# motoko_ice_dragon_v1.net
KiCad netlist of a schematic drawn in EAGLE
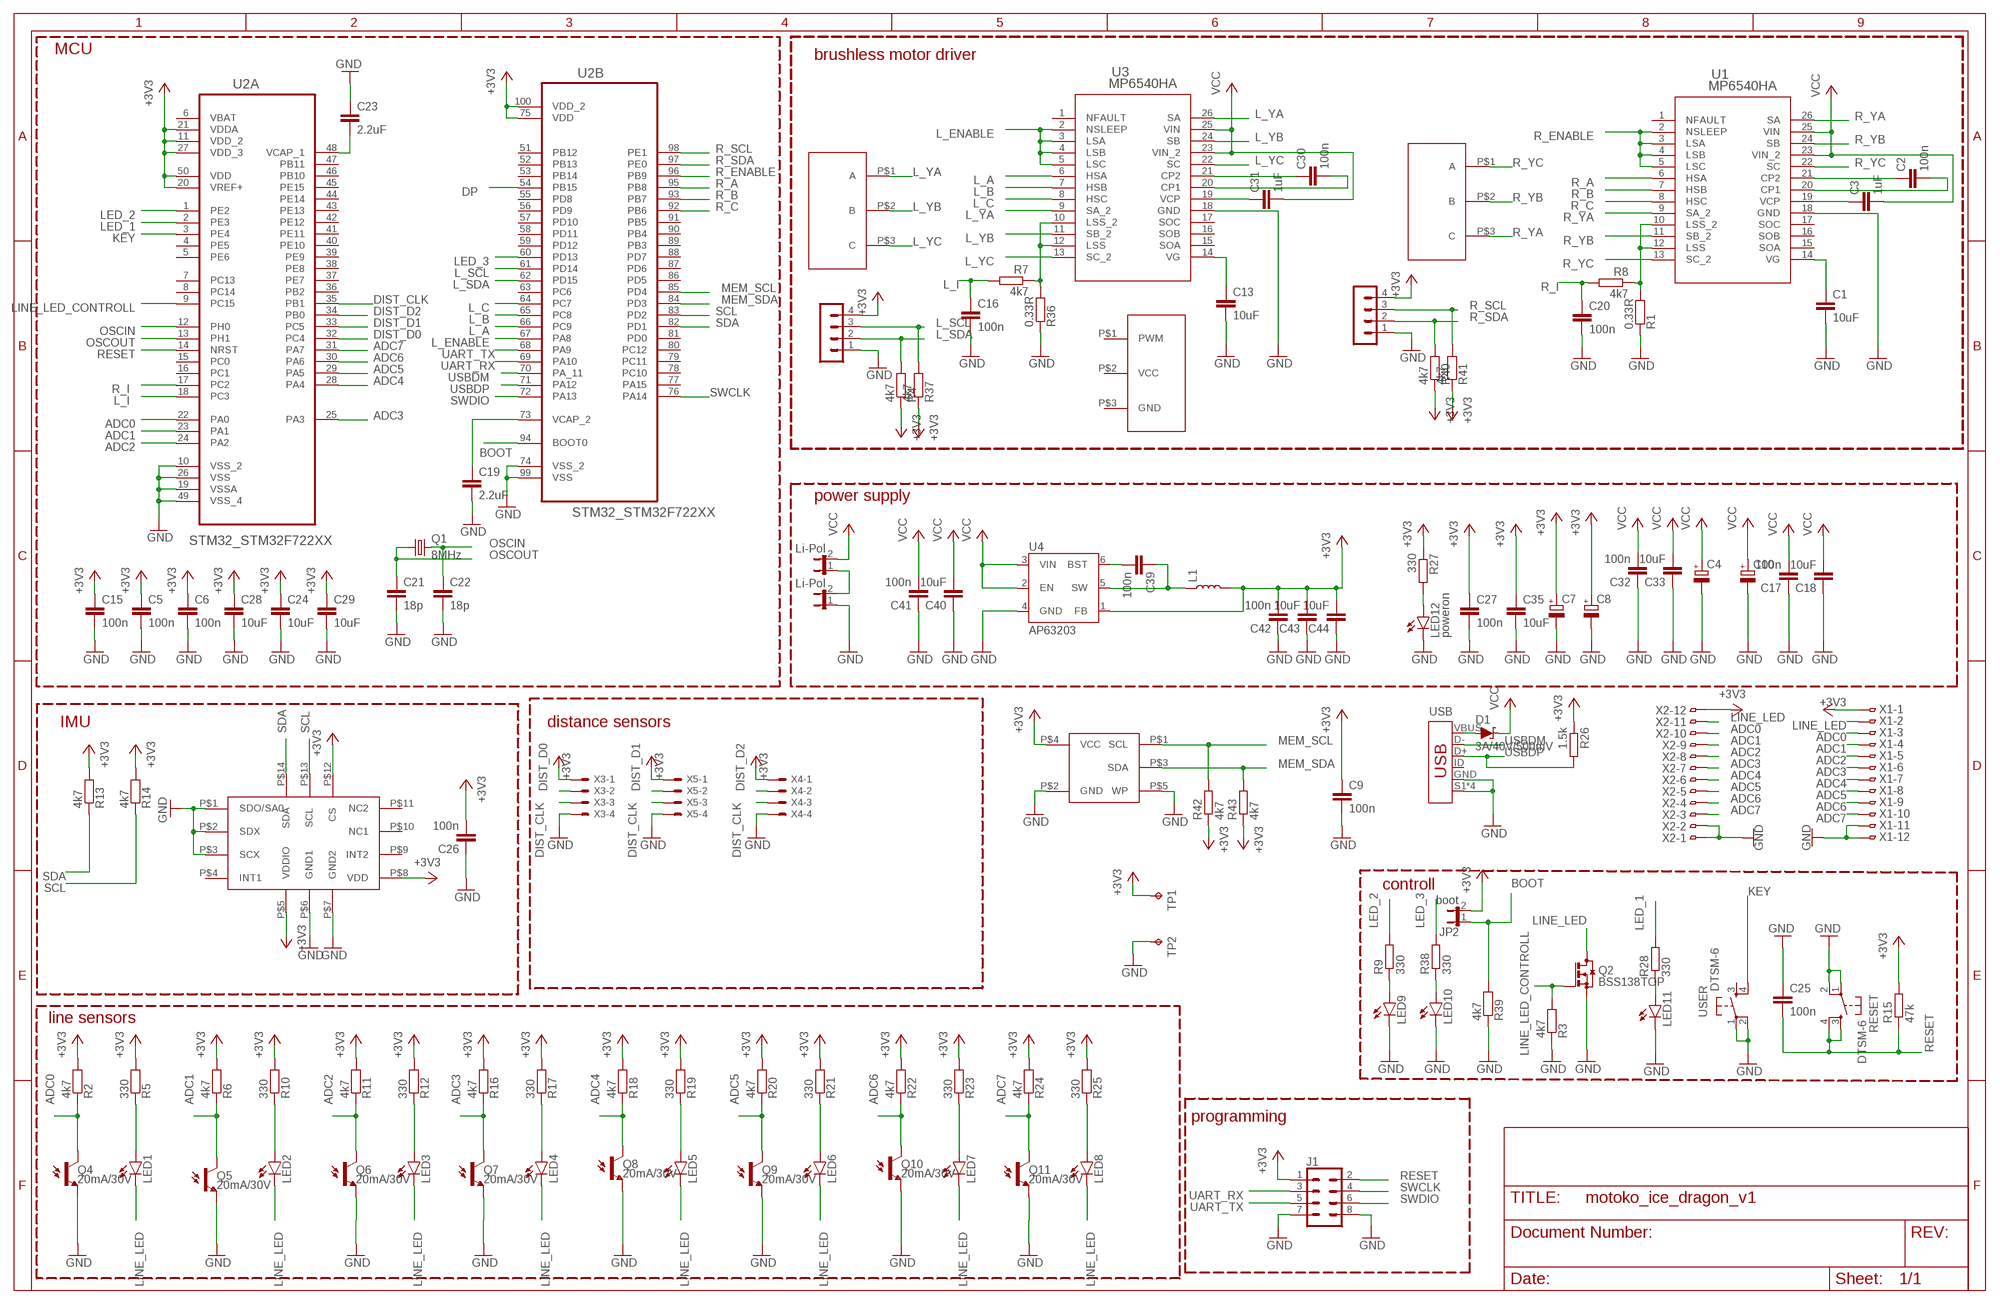
[diagram p0: schematic, sheet 1]

(export (version "E")
  (design (tool "Eeschema 10.0.6"))
  (components
    (comp (ref "C1")
      (value "10uF")
      (footprint "eagle-import:C0805")
      (libsource (lib "eagle-import") (part "C-EUC0805"))
    )
    (comp (ref "C2")
      (value "100n")
      (footprint "eagle-import:C0805")
      (libsource (lib "eagle-import") (part "C-EUC0805"))
    )
    (comp (ref "C3")
      (value "1uF")
      (footprint "eagle-import:C0805")
      (libsource (lib "eagle-import") (part "C-EUC0805"))
    )
    (comp (ref "C4")
      (value "CPOL-EU085CS-1AR")
      (footprint "eagle-import:085CS_1AR")
      (libsource (lib "eagle-import") (part "CPOL-EU085CS-1AR"))
    )
    (comp (ref "C5")
      (value "100n")
      (footprint "eagle-import:C0805")
      (libsource (lib "eagle-import") (part "C-EUC0805"))
    )
    (comp (ref "C6")
      (value "100n")
      (footprint "eagle-import:C0805")
      (libsource (lib "eagle-import") (part "C-EUC0805"))
    )
    (comp (ref "C7")
      (value "CPOL-EU085CS-1AR")
      (footprint "eagle-import:085CS_1AR")
      (libsource (lib "eagle-import") (part "CPOL-EU085CS-1AR"))
    )
    (comp (ref "C8")
      (value "CPOL-EU085CS-1AR")
      (footprint "eagle-import:085CS_1AR")
      (libsource (lib "eagle-import") (part "CPOL-EU085CS-1AR"))
    )
    (comp (ref "C9")
      (value "100n")
      (footprint "eagle-import:C0805")
      (libsource (lib "eagle-import") (part "C-EUC0805"))
    )
    (comp (ref "C10")
      (value "CPOL-EU085CS-1AR")
      (footprint "eagle-import:085CS_1AR")
      (libsource (lib "eagle-import") (part "CPOL-EU085CS-1AR"))
    )
    (comp (ref "C13")
      (value "10uF")
      (footprint "eagle-import:C0805")
      (libsource (lib "eagle-import") (part "C-EUC0805"))
    )
    (comp (ref "C15")
      (value "100n")
      (footprint "eagle-import:C0805")
      (libsource (lib "eagle-import") (part "C-EUC0805"))
    )
    (comp (ref "C16")
      (value "100n")
      (footprint "eagle-import:C0805")
      (libsource (lib "eagle-import") (part "C-EUC0805"))
    )
    (comp (ref "C17")
      (value "100n")
      (footprint "eagle-import:C0805")
      (libsource (lib "eagle-import") (part "C-EUC0805"))
    )
    (comp (ref "C18")
      (value "10uF")
      (footprint "eagle-import:C0805")
      (libsource (lib "eagle-import") (part "C-EUC0805"))
    )
    (comp (ref "C19")
      (value "2.2uF")
      (footprint "eagle-import:C0805")
      (libsource (lib "eagle-import") (part "C-EUC0805"))
    )
    (comp (ref "C20")
      (value "100n")
      (footprint "eagle-import:C0805")
      (libsource (lib "eagle-import") (part "C-EUC0805"))
    )
    (comp (ref "C21")
      (value "18p")
      (footprint "eagle-import:C0805")
      (libsource (lib "eagle-import") (part "C-EUC0805"))
    )
    (comp (ref "C22")
      (value "18p")
      (footprint "eagle-import:C0805")
      (libsource (lib "eagle-import") (part "C-EUC0805"))
    )
    (comp (ref "C23")
      (value "2.2uF")
      (footprint "eagle-import:C0805")
      (libsource (lib "eagle-import") (part "C-EUC0805"))
    )
    (comp (ref "C24")
      (value "10uF")
      (footprint "eagle-import:C0805")
      (libsource (lib "eagle-import") (part "C-EUC0805"))
    )
    (comp (ref "C25")
      (value "100n")
      (footprint "eagle-import:C0805")
      (libsource (lib "eagle-import") (part "C-EUC0805"))
    )
    (comp (ref "C26")
      (value "100n")
      (footprint "eagle-import:C0805")
      (libsource (lib "eagle-import") (part "C-EUC0805"))
    )
    (comp (ref "C27")
      (value "100n")
      (footprint "eagle-import:C0805")
      (libsource (lib "eagle-import") (part "C-EUC0805"))
    )
    (comp (ref "C28")
      (value "10uF")
      (footprint "eagle-import:C0805")
      (libsource (lib "eagle-import") (part "C-EUC0805"))
    )
    (comp (ref "C29")
      (value "10uF")
      (footprint "eagle-import:C0805")
      (libsource (lib "eagle-import") (part "C-EUC0805"))
    )
    (comp (ref "C30")
      (value "100n")
      (footprint "eagle-import:C0805")
      (libsource (lib "eagle-import") (part "C-EUC0805"))
    )
    (comp (ref "C31")
      (value "1uF")
      (footprint "eagle-import:C0805")
      (libsource (lib "eagle-import") (part "C-EUC0805"))
    )
    (comp (ref "C32")
      (value "100n")
      (footprint "eagle-import:C0805")
      (libsource (lib "eagle-import") (part "C-EUC0805"))
    )
    (comp (ref "C33")
      (value "10uF")
      (footprint "eagle-import:C0805")
      (libsource (lib "eagle-import") (part "C-EUC0805"))
    )
    (comp (ref "C35")
      (value "10uF")
      (footprint "eagle-import:C0805")
      (libsource (lib "eagle-import") (part "C-EUC0805"))
    )
    (comp (ref "C39")
      (value "100n")
      (footprint "eagle-import:C0805")
      (libsource (lib "eagle-import") (part "C-EUC0805"))
    )
    (comp (ref "C40")
      (value "10uF")
      (footprint "eagle-import:C0805")
      (libsource (lib "eagle-import") (part "C-EUC0805"))
    )
    (comp (ref "C41")
      (value "100n")
      (footprint "eagle-import:C0805")
      (libsource (lib "eagle-import") (part "C-EUC0805"))
    )
    (comp (ref "C42")
      (value "100n")
      (footprint "eagle-import:C0805")
      (libsource (lib "eagle-import") (part "C-EUC0805"))
    )
    (comp (ref "C43")
      (value "10uF")
      (footprint "eagle-import:C0805")
      (libsource (lib "eagle-import") (part "C-EUC0805"))
    )
    (comp (ref "C44")
      (value "10uF")
      (footprint "eagle-import:C0805")
      (libsource (lib "eagle-import") (part "C-EUC0805"))
    )
    (comp (ref "D1")
      (value "3A/40V/500mV")
      (footprint "eagle-import:SMA-DIODE")
      (libsource (lib "eagle-import") (part "DIODE-SCHOTTKY-B340A"))
    )
    (comp (ref "J1")
      (value "CONN_04X2")
      (footprint "eagle-import:2X4")
      (libsource (lib "eagle-import") (part "CONN_04X2"))
    )
    (comp (ref "JP1")
      (value "Li-Pol")
      (footprint "eagle-import:JP1")
      (libsource (lib "eagle-import") (part "JP1E"))
    )
    (comp (ref "JP2")
      (value "boot")
      (footprint "eagle-import:JP1")
      (libsource (lib "eagle-import") (part "JP1E"))
    )
    (comp (ref "JP3")
      (value "Li-Pol")
      (footprint "eagle-import:JP1")
      (libsource (lib "eagle-import") (part "JP1E"))
    )
    (comp (ref "L1")
      (value "4.7uH, TYS50204R7N-10")
      (footprint "eagle-import:CR54")
      (libsource (lib "eagle-import") (part "INDUCTOR-CR54-3.3UH"))
    )
    (comp (ref "LED1")
      (value "LEDCHIPLED_1206")
      (footprint "eagle-import:CHIPLED_1206")
      (libsource (lib "eagle-import") (part "LEDCHIPLED_1206"))
    )
    (comp (ref "LED2")
      (value "LEDCHIPLED_1206")
      (footprint "eagle-import:CHIPLED_1206")
      (libsource (lib "eagle-import") (part "LEDCHIPLED_1206"))
    )
    (comp (ref "LED3")
      (value "LEDCHIPLED_1206")
      (footprint "eagle-import:CHIPLED_1206")
      (libsource (lib "eagle-import") (part "LEDCHIPLED_1206"))
    )
    (comp (ref "LED4")
      (value "LEDCHIPLED_1206")
      (footprint "eagle-import:CHIPLED_1206")
      (libsource (lib "eagle-import") (part "LEDCHIPLED_1206"))
    )
    (comp (ref "LED5")
      (value "LEDCHIPLED_1206")
      (footprint "eagle-import:CHIPLED_1206")
      (libsource (lib "eagle-import") (part "LEDCHIPLED_1206"))
    )
    (comp (ref "LED6")
      (value "LEDCHIPLED_1206")
      (footprint "eagle-import:CHIPLED_1206")
      (libsource (lib "eagle-import") (part "LEDCHIPLED_1206"))
    )
    (comp (ref "LED7")
      (value "LEDCHIPLED_1206")
      (footprint "eagle-import:CHIPLED_1206")
      (libsource (lib "eagle-import") (part "LEDCHIPLED_1206"))
    )
    (comp (ref "LED8")
      (value "LEDCHIPLED_1206")
      (footprint "eagle-import:CHIPLED_1206")
      (libsource (lib "eagle-import") (part "LEDCHIPLED_1206"))
    )
    (comp (ref "LED9")
      (value "LEDCHIPLED_1206")
      (footprint "eagle-import:CHIPLED_1206")
      (libsource (lib "eagle-import") (part "LEDCHIPLED_1206"))
    )
    (comp (ref "LED10")
      (value "LEDCHIPLED_1206")
      (footprint "eagle-import:CHIPLED_1206")
      (libsource (lib "eagle-import") (part "LEDCHIPLED_1206"))
    )
    (comp (ref "LED11")
      (value "LEDCHIPLED_1206")
      (footprint "eagle-import:CHIPLED_1206")
      (libsource (lib "eagle-import") (part "LEDCHIPLED_1206"))
    )
    (comp (ref "LED12")
      (value "poweron")
      (footprint "eagle-import:CHIPLED_1206")
      (libsource (lib "eagle-import") (part "LEDCHIPLED_1206"))
    )
    (comp (ref "L_ENCODER")
      (value "MA04-1")
      (footprint "eagle-import:MA04-1")
      (libsource (lib "eagle-import") (part "MA04-1"))
    )
    (comp (ref "L_ENCODER1")
      (value "MA04-1")
      (footprint "eagle-import:MA04-1")
      (libsource (lib "eagle-import") (part "MA04-1"))
    )
    (comp (ref "Q1")
      (value "8MHz")
      (footprint "eagle-import:CTS406")
      (libsource (lib "eagle-import") (part "CRYSTALCTS406"))
    )
    (comp (ref "Q2")
      (value "BSS138TOP")
      (footprint "eagle-import:SOT23")
      (libsource (lib "eagle-import") (part "BSS138TOP"))
    )
    (comp (ref "Q4")
      (value "20mA/30V")
      (footprint "eagle-import:PT17-21C-L41-TR8")
      (libsource (lib "eagle-import") (part "PHOTOTRANSISTORPT17-21C-L41-TR8"))
    )
    (comp (ref "Q5")
      (value "20mA/30V")
      (footprint "eagle-import:PT17-21C-L41-TR8")
      (libsource (lib "eagle-import") (part "PHOTOTRANSISTORPT17-21C-L41-TR8"))
    )
    (comp (ref "Q6")
      (value "20mA/30V")
      (footprint "eagle-import:PT17-21C-L41-TR8")
      (libsource (lib "eagle-import") (part "PHOTOTRANSISTORPT17-21C-L41-TR8"))
    )
    (comp (ref "Q7")
      (value "20mA/30V")
      (footprint "eagle-import:PT17-21C-L41-TR8")
      (libsource (lib "eagle-import") (part "PHOTOTRANSISTORPT17-21C-L41-TR8"))
    )
    (comp (ref "Q8")
      (value "20mA/30V")
      (footprint "eagle-import:PT17-21C-L41-TR8")
      (libsource (lib "eagle-import") (part "PHOTOTRANSISTORPT17-21C-L41-TR8"))
    )
    (comp (ref "Q9")
      (value "20mA/30V")
      (footprint "eagle-import:PT17-21C-L41-TR8")
      (libsource (lib "eagle-import") (part "PHOTOTRANSISTORPT17-21C-L41-TR8"))
    )
    (comp (ref "Q10")
      (value "20mA/30V")
      (footprint "eagle-import:PT17-21C-L41-TR8")
      (libsource (lib "eagle-import") (part "PHOTOTRANSISTORPT17-21C-L41-TR8"))
    )
    (comp (ref "Q11")
      (value "20mA/30V")
      (footprint "eagle-import:PT17-21C-L41-TR8")
      (libsource (lib "eagle-import") (part "PHOTOTRANSISTORPT17-21C-L41-TR8"))
    )
    (comp (ref "R1")
      (value "0.33R")
      (footprint "eagle-import:M1206")
      (libsource (lib "eagle-import") (part "R-EU_M1206"))
    )
    (comp (ref "R2")
      (value "4k7")
      (footprint "eagle-import:M0805")
      (libsource (lib "eagle-import") (part "resistor_348_R-EU_M0805"))
    )
    (comp (ref "R3")
      (value "4k7")
      (footprint "eagle-import:M0805")
      (libsource (lib "eagle-import") (part "resistor_348_R-EU_M0805"))
    )
    (comp (ref "R4")
      (value "4k7")
      (footprint "eagle-import:M0805")
      (libsource (lib "eagle-import") (part "resistor_348_R-EU_M0805"))
    )
    (comp (ref "R5")
      (value "330")
      (footprint "eagle-import:M0805")
      (libsource (lib "eagle-import") (part "resistor_348_R-EU_M0805"))
    )
    (comp (ref "R6")
      (value "4k7")
      (footprint "eagle-import:M0805")
      (libsource (lib "eagle-import") (part "resistor_348_R-EU_M0805"))
    )
    (comp (ref "R7")
      (value "4k7")
      (footprint "eagle-import:M0805")
      (libsource (lib "eagle-import") (part "resistor_348_R-EU_M0805"))
    )
    (comp (ref "R8")
      (value "4k7")
      (footprint "eagle-import:M0805")
      (libsource (lib "eagle-import") (part "resistor_348_R-EU_M0805"))
    )
    (comp (ref "R9")
      (value "330")
      (footprint "eagle-import:M0805")
      (libsource (lib "eagle-import") (part "resistor_348_R-EU_M0805"))
    )
    (comp (ref "R10")
      (value "330")
      (footprint "eagle-import:M0805")
      (libsource (lib "eagle-import") (part "resistor_348_R-EU_M0805"))
    )
    (comp (ref "R11")
      (value "4k7")
      (footprint "eagle-import:M0805")
      (libsource (lib "eagle-import") (part "resistor_348_R-EU_M0805"))
    )
    (comp (ref "R12")
      (value "330")
      (footprint "eagle-import:M0805")
      (libsource (lib "eagle-import") (part "resistor_348_R-EU_M0805"))
    )
    (comp (ref "R13")
      (value "4k7")
      (footprint "eagle-import:M0805")
      (libsource (lib "eagle-import") (part "resistor_348_R-EU_M0805"))
    )
    (comp (ref "R14")
      (value "4k7")
      (footprint "eagle-import:M0805")
      (libsource (lib "eagle-import") (part "resistor_348_R-EU_M0805"))
    )
    (comp (ref "R15")
      (value "47k")
      (footprint "eagle-import:M0805")
      (libsource (lib "eagle-import") (part "resistor_348_R-EU_M0805"))
    )
    (comp (ref "R16")
      (value "4k7")
      (footprint "eagle-import:M0805")
      (libsource (lib "eagle-import") (part "resistor_348_R-EU_M0805"))
    )
    (comp (ref "R17")
      (value "330")
      (footprint "eagle-import:M0805")
      (libsource (lib "eagle-import") (part "resistor_348_R-EU_M0805"))
    )
    (comp (ref "R18")
      (value "4k7")
      (footprint "eagle-import:M0805")
      (libsource (lib "eagle-import") (part "resistor_348_R-EU_M0805"))
    )
    (comp (ref "R19")
      (value "330")
      (footprint "eagle-import:M0805")
      (libsource (lib "eagle-import") (part "resistor_348_R-EU_M0805"))
    )
    (comp (ref "R20")
      (value "4k7")
      (footprint "eagle-import:M0805")
      (libsource (lib "eagle-import") (part "resistor_348_R-EU_M0805"))
    )
    (comp (ref "R21")
      (value "330")
      (footprint "eagle-import:M0805")
      (libsource (lib "eagle-import") (part "resistor_348_R-EU_M0805"))
    )
    (comp (ref "R22")
      (value "4k7")
      (footprint "eagle-import:M0805")
      (libsource (lib "eagle-import") (part "resistor_348_R-EU_M0805"))
    )
    (comp (ref "R23")
      (value "330")
      (footprint "eagle-import:M0805")
      (libsource (lib "eagle-import") (part "resistor_348_R-EU_M0805"))
    )
    (comp (ref "R24")
      (value "4k7")
      (footprint "eagle-import:M0805")
      (libsource (lib "eagle-import") (part "resistor_348_R-EU_M0805"))
    )
    (comp (ref "R25")
      (value "330")
      (footprint "eagle-import:M0805")
      (libsource (lib "eagle-import") (part "resistor_348_R-EU_M0805"))
    )
    (comp (ref "R26")
      (value "1.5k")
      (footprint "eagle-import:M0805")
      (libsource (lib "eagle-import") (part "resistor_348_R-EU_M0805"))
    )
    (comp (ref "R27")
      (value "330")
      (footprint "eagle-import:M0805")
      (libsource (lib "eagle-import") (part "resistor_348_R-EU_M0805"))
    )
    (comp (ref "R28")
      (value "330")
      (footprint "eagle-import:M0805")
      (libsource (lib "eagle-import") (part "resistor_348_R-EU_M0805"))
    )
    (comp (ref "R36")
      (value "0.33R")
      (footprint "eagle-import:M1206")
      (libsource (lib "eagle-import") (part "R-EU_M1206"))
    )
    (comp (ref "R37")
      (value "4k7")
      (footprint "eagle-import:M0805")
      (libsource (lib "eagle-import") (part "resistor_348_R-EU_M0805"))
    )
    (comp (ref "R38")
      (value "330")
      (footprint "eagle-import:M0805")
      (libsource (lib "eagle-import") (part "resistor_348_R-EU_M0805"))
    )
    (comp (ref "R39")
      (value "4k7")
      (footprint "eagle-import:M0805")
      (libsource (lib "eagle-import") (part "resistor_348_R-EU_M0805"))
    )
    (comp (ref "R40")
      (value "4k7")
      (footprint "eagle-import:M0805")
      (libsource (lib "eagle-import") (part "resistor_348_R-EU_M0805"))
    )
    (comp (ref "R41")
      (value "4k7")
      (footprint "eagle-import:M0805")
      (libsource (lib "eagle-import") (part "resistor_348_R-EU_M0805"))
    )
    (comp (ref "R42")
      (value "4k7")
      (footprint "eagle-import:M0805")
      (libsource (lib "eagle-import") (part "R-EU_M0805"))
    )
    (comp (ref "R43")
      (value "4k7")
      (footprint "eagle-import:M0805")
      (libsource (lib "eagle-import") (part "R-EU_M0805"))
    )
    (comp (ref "RESET")
      (value "DTSM-6")
      (footprint "eagle-import:DTSM-6")
      (libsource (lib "eagle-import") (part "DTSM-6"))
    )
    (comp (ref "TP1")
      (value "TPB1,27")
      (footprint "eagle-import:B1,27")
      (libsource (lib "eagle-import") (part "TPB1,27"))
    )
    (comp (ref "TP2")
      (value "TPB1,27")
      (footprint "eagle-import:B1,27")
      (libsource (lib "eagle-import") (part "TPB1,27"))
    )
    (comp (ref "U$1")
      (value "BRUSHLESS_MOTOR_WHEEL")
      (footprint "eagle-import:BRUSHLESS_MOTOR_WHEEL")
      (libsource (lib "eagle-import") (part "BRUSHLESS_MOTOR_WHEEL"))
    )
    (comp (ref "U$2")
      (value "BRUSHLESS_MOTOR_WHEEL")
      (footprint "eagle-import:BRUSHLESS_MOTOR_WHEEL")
      (libsource (lib "eagle-import") (part "BRUSHLESS_MOTOR_WHEEL"))
    )
    (comp (ref "U$3")
      (value "LSM6DSM")
      (footprint "eagle-import:LGA14L")
      (libsource (lib "eagle-import") (part "LSM6DSM"))
    )
    (comp (ref "U$4")
      (value "24LC24_SOT23")
      (footprint "eagle-import:SOT23")
      (libsource (lib "eagle-import") (part "24LC24_SOT23"))
    )
    (comp (ref "U$5")
      (value "DUCTED_FAN_35MM")
      (footprint "eagle-import:DUCTED_FAN_35MM")
      (libsource (lib "eagle-import") (part "DUCTED_FAN_35MM"))
    )
    (comp (ref "U1")
      (value "MP6540HA")
      (footprint "eagle-import:QFN-5X5_MP6540HA_MNP")
      (fields (field (name "COPYRIGHT") "Copyright (C) 2018 Accelerated Designs. All rights reserved"))
      (libsource (lib "eagle-import") (part "MP6540HA"))
    )
    (comp (ref "U2")
      (value "STM32_STM32F722XX")
      (footprint "eagle-import:STM32_QFP50P1600X1600X160-100N")
      (fields (field (name "MPN") "STM32F407VET6"))
      (libsource (lib "eagle-import") (part "STM32_STM32F722XX"))
    )
    (comp (ref "U3")
      (value "MP6540HA")
      (footprint "eagle-import:QFN-5X5_MP6540HA_MNP")
      (fields (field (name "COPYRIGHT") "Copyright (C) 2018 Accelerated Designs. All rights reserved"))
      (libsource (lib "eagle-import") (part "MP6540HA"))
    )
    (comp (ref "U4")
      (value "AP63203")
      (footprint "eagle-import:SOT23-6")
      (libsource (lib "eagle-import") (part "AP63203"))
    )
    (comp (ref "USB")
      (value "USB_MINI-B_SMT")
      (footprint "eagle-import:USB-MINIB")
      (libsource (lib "eagle-import") (part "USB_MINI-B_SMT"))
    )
    (comp (ref "USER")
      (value "DTSM-6")
      (footprint "eagle-import:DTSM-6")
      (libsource (lib "eagle-import") (part "DTSM-6"))
    )
    (comp (ref "X1")
      (value "FH12-12S-0.5SH")
      (footprint "eagle-import:FH12-12S-0.5SH")
      (fields (field (name "MPN") "FH12-12S-0.5SH(55)"))
      (libsource (lib "eagle-import") (part "FH12-12S-0.5SH"))
    )
    (comp (ref "X2")
      (value "FH12-12S-0.5SH")
      (footprint "eagle-import:FH12-12S-0.5SH")
      (fields (field (name "MPN") "FH12-12S-0.5SH(55)"))
      (libsource (lib "eagle-import") (part "FH12-12S-0.5SH"))
    )
    (comp (ref "X3")
      (value "52745-0490")
      (footprint "eagle-import:52745-0490")
      (fields (field (name "MF") "MOLEX"))
      (libsource (lib "eagle-import") (part "52745-0490"))
    )
    (comp (ref "X4")
      (value "52745-0490")
      (footprint "eagle-import:52745-0490")
      (fields (field (name "MF") "MOLEX"))
      (libsource (lib "eagle-import") (part "52745-0490"))
    )
    (comp (ref "X5")
      (value "52745-0490")
      (footprint "eagle-import:52745-0490")
      (fields (field (name "MF") "MOLEX"))
      (libsource (lib "eagle-import") (part "52745-0490"))
    )
  )
  (nets
    (net (code "1") (name "+3V3") (class "Default")
      (node (ref "C15") (pin "1") (pinfunction "1_1") (pintype "passive"))
      (node (ref "C24") (pin "1") (pinfunction "1_1") (pintype "passive"))
      (node (ref "C26") (pin "2") (pinfunction "2_2") (pintype "passive"))
      (node (ref "C27") (pin "1") (pinfunction "1_1") (pintype "passive"))
      (node (ref "C28") (pin "1") (pinfunction "1_1") (pintype "passive"))
      (node (ref "C29") (pin "1") (pinfunction "1_1") (pintype "passive"))
      (node (ref "C35") (pin "1") (pinfunction "1_1") (pintype "passive"))
      (node (ref "C42") (pin "2") (pinfunction "2_2") (pintype "passive"))
      (node (ref "C43") (pin "2") (pinfunction "2_2") (pintype "passive"))
      (node (ref "C44") (pin "2") (pinfunction "2_2") (pintype "passive"))
      (node (ref "C5") (pin "1") (pinfunction "1_1") (pintype "passive"))
      (node (ref "C6") (pin "1") (pinfunction "1_1") (pintype "passive"))
      (node (ref "C7") (pin "+") (pinfunction "+_+") (pintype "passive"))
      (node (ref "C8") (pin "+") (pinfunction "+_+") (pintype "passive"))
      (node (ref "C9") (pin "1") (pinfunction "1_1") (pintype "passive"))
      (node (ref "J1") (pin "1") (pinfunction "1_1") (pintype "passive"))
      (node (ref "JP2") (pin "2") (pinfunction "2_2") (pintype "passive"))
      (node (ref "L1") (pin "P$2") (pinfunction "2_P$2") (pintype "passive"))
      (node (ref "L_ENCODER") (pin "4") (pinfunction "4_4") (pintype "passive"))
      (node (ref "L_ENCODER1") (pin "4") (pinfunction "4_4") (pintype "passive"))
      (node (ref "R10") (pin "2") (pinfunction "2_2") (pintype "passive"))
      (node (ref "R11") (pin "2") (pinfunction "2_2") (pintype "passive"))
      (node (ref "R12") (pin "2") (pinfunction "2_2") (pintype "passive"))
      (node (ref "R13") (pin "2") (pinfunction "2_2") (pintype "passive"))
      (node (ref "R14") (pin "2") (pinfunction "2_2") (pintype "passive"))
      (node (ref "R15") (pin "2") (pinfunction "2_2") (pintype "passive"))
      (node (ref "R16") (pin "2") (pinfunction "2_2") (pintype "passive"))
      (node (ref "R17") (pin "2") (pinfunction "2_2") (pintype "passive"))
      (node (ref "R18") (pin "2") (pinfunction "2_2") (pintype "passive"))
      (node (ref "R19") (pin "2") (pinfunction "2_2") (pintype "passive"))
      (node (ref "R2") (pin "2") (pinfunction "2_2") (pintype "passive"))
      (node (ref "R20") (pin "2") (pinfunction "2_2") (pintype "passive"))
      (node (ref "R21") (pin "2") (pinfunction "2_2") (pintype "passive"))
      (node (ref "R22") (pin "2") (pinfunction "2_2") (pintype "passive"))
      (node (ref "R23") (pin "2") (pinfunction "2_2") (pintype "passive"))
      (node (ref "R24") (pin "2") (pinfunction "2_2") (pintype "passive"))
      (node (ref "R25") (pin "2") (pinfunction "2_2") (pintype "passive"))
      (node (ref "R26") (pin "1") (pinfunction "1_1") (pintype "passive"))
      (node (ref "R27") (pin "1") (pinfunction "1_1") (pintype "passive"))
      (node (ref "R37") (pin "1") (pinfunction "1_1") (pintype "passive"))
      (node (ref "R4") (pin "1") (pinfunction "1_1") (pintype "passive"))
      (node (ref "R40") (pin "1") (pinfunction "1_1") (pintype "passive"))
      (node (ref "R41") (pin "1") (pinfunction "1_1") (pintype "passive"))
      (node (ref "R42") (pin "1") (pinfunction "1_1") (pintype "passive"))
      (node (ref "R43") (pin "1") (pinfunction "1_1") (pintype "passive"))
      (node (ref "R5") (pin "2") (pinfunction "2_2") (pintype "passive"))
      (node (ref "R6") (pin "2") (pinfunction "2_2") (pintype "passive"))
      (node (ref "TP1") (pin "TP") (pinfunction "TP_TP") (pintype "input"))
      (node (ref "U$3") (pin "P$12") (pinfunction "CS_P$12") (pintype "bidirectional"))
      (node (ref "U$3") (pin "P$5") (pinfunction "VDDIO_P$5") (pintype "bidirectional"))
      (node (ref "U$3") (pin "P$8") (pinfunction "VDD_P$8") (pintype "bidirectional"))
      (node (ref "U$4") (pin "P$4") (pinfunction "VCC_P$4") (pintype "bidirectional"))
      (node (ref "U2") (pin "100") (pinfunction "VDD_2_100") (pintype "power_in"))
      (node (ref "U2") (pin "11") (pinfunction "VDD_2_11") (pintype "power_in"))
      (node (ref "U2") (pin "20") (pinfunction "VREF+_20") (pintype "power_in"))
      (node (ref "U2") (pin "21") (pinfunction "VDDA_21") (pintype "power_in"))
      (node (ref "U2") (pin "27") (pinfunction "VDD_3_27") (pintype "power_in"))
      (node (ref "U2") (pin "50") (pinfunction "VDD_50") (pintype "power_in"))
      (node (ref "U2") (pin "75") (pinfunction "VDD_75") (pintype "power_in"))
      (node (ref "U4") (pin "1") (pinfunction "FB_1") (pintype "bidirectional"))
      (node (ref "X1") (pin "1") (pinfunction "1_1") (pintype "passive"))
      (node (ref "X2") (pin "12") (pinfunction "1_12") (pintype "passive"))
      (node (ref "X3") (pin "1") (pinfunction "S_1") (pintype "passive"))
      (node (ref "X4") (pin "1") (pinfunction "S_1") (pintype "passive"))
      (node (ref "X5") (pin "1") (pinfunction "S_1") (pintype "passive"))
    )
    (net (code "2") (name "/ADC0") (class "Default")
      (node (ref "Q4") (pin "C") (pinfunction "C_C") (pintype "passive"))
      (node (ref "R2") (pin "1") (pinfunction "1_1") (pintype "passive"))
      (node (ref "U2") (pin "22") (pinfunction "PA0_22") (pintype "bidirectional"))
      (node (ref "X1") (pin "3") (pinfunction "1_3") (pintype "passive"))
      (node (ref "X2") (pin "10") (pinfunction "1_10") (pintype "passive"))
    )
    (net (code "3") (name "/ADC1") (class "Default")
      (node (ref "Q5") (pin "C") (pinfunction "C_C") (pintype "passive"))
      (node (ref "R6") (pin "1") (pinfunction "1_1") (pintype "passive"))
      (node (ref "U2") (pin "23") (pinfunction "PA1_23") (pintype "bidirectional"))
      (node (ref "X1") (pin "4") (pinfunction "1_4") (pintype "passive"))
      (node (ref "X2") (pin "9") (pinfunction "1_9") (pintype "passive"))
    )
    (net (code "4") (name "/ADC2") (class "Default")
      (node (ref "Q6") (pin "C") (pinfunction "C_C") (pintype "passive"))
      (node (ref "R11") (pin "1") (pinfunction "1_1") (pintype "passive"))
      (node (ref "U2") (pin "24") (pinfunction "PA2_24") (pintype "bidirectional"))
      (node (ref "X1") (pin "5") (pinfunction "1_5") (pintype "passive"))
      (node (ref "X2") (pin "8") (pinfunction "1_8") (pintype "passive"))
    )
    (net (code "5") (name "/ADC3") (class "Default")
      (node (ref "Q7") (pin "C") (pinfunction "C_C") (pintype "passive"))
      (node (ref "R16") (pin "1") (pinfunction "1_1") (pintype "passive"))
      (node (ref "U2") (pin "25") (pinfunction "PA3_25") (pintype "bidirectional"))
      (node (ref "X1") (pin "6") (pinfunction "1_6") (pintype "passive"))
      (node (ref "X2") (pin "7") (pinfunction "1_7") (pintype "passive"))
    )
    (net (code "6") (name "/ADC4") (class "Default")
      (node (ref "Q8") (pin "C") (pinfunction "C_C") (pintype "passive"))
      (node (ref "R18") (pin "1") (pinfunction "1_1") (pintype "passive"))
      (node (ref "U2") (pin "28") (pinfunction "PA4_28") (pintype "bidirectional"))
      (node (ref "X1") (pin "7") (pinfunction "1_7") (pintype "passive"))
      (node (ref "X2") (pin "6") (pinfunction "1_6") (pintype "passive"))
    )
    (net (code "7") (name "/ADC5") (class "Default")
      (node (ref "Q9") (pin "C") (pinfunction "C_C") (pintype "passive"))
      (node (ref "R20") (pin "1") (pinfunction "1_1") (pintype "passive"))
      (node (ref "U2") (pin "29") (pinfunction "PA5_29") (pintype "bidirectional"))
      (node (ref "X1") (pin "8") (pinfunction "1_8") (pintype "passive"))
      (node (ref "X2") (pin "5") (pinfunction "1_5") (pintype "passive"))
    )
    (net (code "8") (name "/ADC6") (class "Default")
      (node (ref "Q10") (pin "C") (pinfunction "C_C") (pintype "passive"))
      (node (ref "R22") (pin "1") (pinfunction "1_1") (pintype "passive"))
      (node (ref "U2") (pin "30") (pinfunction "PA6_30") (pintype "bidirectional"))
      (node (ref "X1") (pin "9") (pinfunction "1_9") (pintype "passive"))
      (node (ref "X2") (pin "4") (pinfunction "1_4") (pintype "passive"))
    )
    (net (code "9") (name "/ADC7") (class "Default")
      (node (ref "Q11") (pin "C") (pinfunction "C_C") (pintype "passive"))
      (node (ref "R24") (pin "1") (pinfunction "1_1") (pintype "passive"))
      (node (ref "U2") (pin "31") (pinfunction "PA7_31") (pintype "bidirectional"))
      (node (ref "X1") (pin "10") (pinfunction "1_10") (pintype "passive"))
      (node (ref "X2") (pin "3") (pinfunction "1_3") (pintype "passive"))
    )
    (net (code "10") (name "/BOOT") (class "Default")
      (node (ref "JP2") (pin "1") (pinfunction "1_1") (pintype "passive"))
      (node (ref "R39") (pin "2") (pinfunction "2_2") (pintype "passive"))
      (node (ref "U2") (pin "94") (pinfunction "BOOT0_94") (pintype "input"))
    )
    (net (code "11") (name "/DIST_CLK") (class "Default")
      (node (ref "U2") (pin "35") (pinfunction "PB1_35") (pintype "bidirectional"))
      (node (ref "X3") (pin "3") (pinfunction "S_3") (pintype "passive"))
      (node (ref "X4") (pin "3") (pinfunction "S_3") (pintype "passive"))
      (node (ref "X5") (pin "3") (pinfunction "S_3") (pintype "passive"))
    )
    (net (code "12") (name "/DIST_D0") (class "Default")
      (node (ref "U2") (pin "32") (pinfunction "PC4_32") (pintype "bidirectional"))
      (node (ref "X3") (pin "2") (pinfunction "S_2") (pintype "passive"))
    )
    (net (code "13") (name "/DIST_D1") (class "Default")
      (node (ref "U2") (pin "33") (pinfunction "PC5_33") (pintype "bidirectional"))
      (node (ref "X5") (pin "2") (pinfunction "S_2") (pintype "passive"))
    )
    (net (code "14") (name "/DIST_D2") (class "Default")
      (node (ref "U2") (pin "34") (pinfunction "PB0_34") (pintype "bidirectional"))
      (node (ref "X4") (pin "2") (pinfunction "S_2") (pintype "passive"))
    )
    (net (code "15") (name "/DP") (class "Default")
      (node (ref "U2") (pin "54") (pinfunction "PB15_54") (pintype "bidirectional"))
    )
    (net (code "16") (name "/KEY") (class "Default")
      (node (ref "U2") (pin "3") (pinfunction "PE4_3") (pintype "bidirectional"))
      (node (ref "USER") (pin "4") (pinfunction "4_4") (pintype "passive"))
    )
    (net (code "17") (name "/LED_1") (class "Default")
      (node (ref "R28") (pin "2") (pinfunction "2_2") (pintype "passive"))
      (node (ref "U2") (pin "2") (pinfunction "PE3_2") (pintype "bidirectional"))
    )
    (net (code "18") (name "/LED_2") (class "Default")
      (node (ref "R9") (pin "2") (pinfunction "2_2") (pintype "passive"))
      (node (ref "U2") (pin "1") (pinfunction "PE2_1") (pintype "bidirectional"))
    )
    (net (code "19") (name "/LED_3") (class "Default")
      (node (ref "R38") (pin "2") (pinfunction "2_2") (pintype "passive"))
      (node (ref "U2") (pin "60") (pinfunction "PD13_60") (pintype "bidirectional"))
    )
    (net (code "20") (name "/LINE_LED") (class "Default")
      (node (ref "LED1") (pin "C") (pinfunction "C_C") (pintype "passive"))
      (node (ref "LED2") (pin "C") (pinfunction "C_C") (pintype "passive"))
      (node (ref "LED3") (pin "C") (pinfunction "C_C") (pintype "passive"))
      (node (ref "LED4") (pin "C") (pinfunction "C_C") (pintype "passive"))
      (node (ref "LED5") (pin "C") (pinfunction "C_C") (pintype "passive"))
      (node (ref "LED6") (pin "C") (pinfunction "C_C") (pintype "passive"))
      (node (ref "LED7") (pin "C") (pinfunction "C_C") (pintype "passive"))
      (node (ref "LED8") (pin "C") (pinfunction "C_C") (pintype "passive"))
      (node (ref "Q2") (pin "3") (pinfunction "D_3") (pintype "passive"))
      (node (ref "X1") (pin "2") (pinfunction "1_2") (pintype "passive"))
      (node (ref "X2") (pin "11") (pinfunction "1_11") (pintype "passive"))
    )
    (net (code "21") (name "/LINE_LED_CONTROLL") (class "Default")
      (node (ref "Q2") (pin "1") (pinfunction "G_1") (pintype "passive"))
      (node (ref "R3") (pin "2") (pinfunction "2_2") (pintype "passive"))
      (node (ref "U2") (pin "9") (pinfunction "PC15_9") (pintype "bidirectional"))
    )
    (net (code "22") (name "/L_A") (class "Default")
      (node (ref "U2") (pin "66") (pinfunction "PC9_66") (pintype "bidirectional"))
      (node (ref "U3") (pin "6") (pinfunction "HSA_6") (pintype "passive"))
    )
    (net (code "23") (name "/L_B") (class "Default")
      (node (ref "U2") (pin "65") (pinfunction "PC8_65") (pintype "bidirectional"))
      (node (ref "U3") (pin "7") (pinfunction "HSB_7") (pintype "passive"))
    )
    (net (code "24") (name "/L_C") (class "Default")
      (node (ref "U2") (pin "64") (pinfunction "PC7_64") (pintype "bidirectional"))
      (node (ref "U3") (pin "8") (pinfunction "HSC_8") (pintype "passive"))
    )
    (net (code "25") (name "/L_ENABLE") (class "Default")
      (node (ref "U2") (pin "67") (pinfunction "PA8_67") (pintype "bidirectional"))
      (node (ref "U3") (pin "2") (pinfunction "NSLEEP_2") (pintype "input"))
      (node (ref "U3") (pin "3") (pinfunction "LSA_3") (pintype "passive"))
      (node (ref "U3") (pin "4") (pinfunction "LSB_4") (pintype "passive"))
      (node (ref "U3") (pin "5") (pinfunction "LSC_5") (pintype "passive"))
    )
    (net (code "26") (name "/L_I") (class "Default")
      (node (ref "C16") (pin "1") (pinfunction "1_1") (pintype "passive"))
      (node (ref "R7") (pin "2") (pinfunction "2_2") (pintype "passive"))
      (node (ref "U2") (pin "18") (pinfunction "PC3_18") (pintype "bidirectional"))
    )
    (net (code "27") (name "/L_SCL") (class "Default")
      (node (ref "L_ENCODER") (pin "3") (pinfunction "3_3") (pintype "passive"))
      (node (ref "R37") (pin "2") (pinfunction "2_2") (pintype "passive"))
      (node (ref "U2") (pin "61") (pinfunction "PD14_61") (pintype "bidirectional"))
    )
    (net (code "28") (name "/L_SDA") (class "Default")
      (node (ref "L_ENCODER") (pin "2") (pinfunction "2_2") (pintype "passive"))
      (node (ref "R4") (pin "2") (pinfunction "2_2") (pintype "passive"))
      (node (ref "U2") (pin "62") (pinfunction "PD15_62") (pintype "bidirectional"))
    )
    (net (code "29") (name "/L_YA") (class "Default")
      (node (ref "U$1") (pin "P$1") (pinfunction "A_P$1") (pintype "input"))
      (node (ref "U3") (pin "26") (pinfunction "SA_26") (pintype "output"))
      (node (ref "U3") (pin "9") (pinfunction "SA_2_9") (pintype "output"))
    )
    (net (code "30") (name "/L_YB") (class "Default")
      (node (ref "U$1") (pin "P$2") (pinfunction "B_P$2") (pintype "input"))
      (node (ref "U3") (pin "11") (pinfunction "SB_2_11") (pintype "output"))
      (node (ref "U3") (pin "24") (pinfunction "SB_24") (pintype "output"))
    )
    (net (code "31") (name "/L_YC") (class "Default")
      (node (ref "U$1") (pin "P$3") (pinfunction "C_P$3") (pintype "input"))
      (node (ref "U3") (pin "13") (pinfunction "SC_2_13") (pintype "output"))
      (node (ref "U3") (pin "22") (pinfunction "SC_22") (pintype "output"))
    )
    (net (code "32") (name "/MEM_SCL") (class "Default")
      (node (ref "R42") (pin "2") (pinfunction "2_2") (pintype "passive"))
      (node (ref "U$4") (pin "P$1") (pinfunction "SCL_P$1") (pintype "bidirectional"))
      (node (ref "U2") (pin "85") (pinfunction "PD4_85") (pintype "bidirectional"))
    )
    (net (code "33") (name "/MEM_SDA") (class "Default")
      (node (ref "R43") (pin "2") (pinfunction "2_2") (pintype "passive"))
      (node (ref "U$4") (pin "P$3") (pinfunction "SDA_P$3") (pintype "bidirectional"))
      (node (ref "U2") (pin "84") (pinfunction "PD3_84") (pintype "bidirectional"))
    )
    (net (code "34") (name "/OSCIN") (class "Default")
      (node (ref "C22") (pin "1") (pinfunction "1_1") (pintype "passive"))
      (node (ref "Q1") (pin "3") (pinfunction "2_3") (pintype "passive"))
      (node (ref "U2") (pin "12") (pinfunction "PH0_12") (pintype "bidirectional"))
    )
    (net (code "35") (name "/OSCOUT") (class "Default")
      (node (ref "C21") (pin "1") (pinfunction "1_1") (pintype "passive"))
      (node (ref "Q1") (pin "1") (pinfunction "1_1") (pintype "passive"))
      (node (ref "U2") (pin "13") (pinfunction "PH1_13") (pintype "bidirectional"))
    )
    (net (code "36") (name "/RESET") (class "Default")
      (node (ref "C25") (pin "2") (pinfunction "2_2") (pintype "passive"))
      (node (ref "J1") (pin "2") (pinfunction "2_2") (pintype "passive"))
      (node (ref "R15") (pin "1") (pinfunction "1_1") (pintype "passive"))
      (node (ref "RESET") (pin "3") (pinfunction "3_3") (pintype "passive"))
      (node (ref "RESET") (pin "4") (pinfunction "4_4") (pintype "passive"))
      (node (ref "U2") (pin "14") (pinfunction "NRST_14") (pintype "bidirectional"))
    )
    (net (code "37") (name "/R_A") (class "Default")
      (node (ref "U1") (pin "6") (pinfunction "HSA_6") (pintype "passive"))
      (node (ref "U2") (pin "95") (pinfunction "PB8_95") (pintype "bidirectional"))
    )
    (net (code "38") (name "/R_B") (class "Default")
      (node (ref "U1") (pin "7") (pinfunction "HSB_7") (pintype "passive"))
      (node (ref "U2") (pin "93") (pinfunction "PB7_93") (pintype "bidirectional"))
    )
    (net (code "39") (name "/R_C") (class "Default")
      (node (ref "U1") (pin "8") (pinfunction "HSC_8") (pintype "passive"))
      (node (ref "U2") (pin "92") (pinfunction "PB6_92") (pintype "bidirectional"))
    )
    (net (code "40") (name "/R_ENABLE") (class "Default")
      (node (ref "U1") (pin "2") (pinfunction "NSLEEP_2") (pintype "input"))
      (node (ref "U1") (pin "3") (pinfunction "LSA_3") (pintype "passive"))
      (node (ref "U1") (pin "4") (pinfunction "LSB_4") (pintype "passive"))
      (node (ref "U1") (pin "5") (pinfunction "LSC_5") (pintype "passive"))
      (node (ref "U2") (pin "96") (pinfunction "PB9_96") (pintype "bidirectional"))
    )
    (net (code "41") (name "/R_I") (class "Default")
      (node (ref "C20") (pin "1") (pinfunction "1_1") (pintype "passive"))
      (node (ref "R8") (pin "2") (pinfunction "2_2") (pintype "passive"))
      (node (ref "U2") (pin "17") (pinfunction "PC2_17") (pintype "bidirectional"))
    )
    (net (code "42") (name "/R_SCL") (class "Default")
      (node (ref "L_ENCODER1") (pin "3") (pinfunction "3_3") (pintype "passive"))
      (node (ref "R41") (pin "2") (pinfunction "2_2") (pintype "passive"))
      (node (ref "U2") (pin "98") (pinfunction "PE1_98") (pintype "bidirectional"))
    )
    (net (code "43") (name "/R_SDA") (class "Default")
      (node (ref "L_ENCODER1") (pin "2") (pinfunction "2_2") (pintype "passive"))
      (node (ref "R40") (pin "2") (pinfunction "2_2") (pintype "passive"))
      (node (ref "U2") (pin "97") (pinfunction "PE0_97") (pintype "bidirectional"))
    )
    (net (code "44") (name "/R_YA") (class "Default")
      (node (ref "U$2") (pin "P$3") (pinfunction "C_P$3") (pintype "input"))
      (node (ref "U1") (pin "26") (pinfunction "SA_26") (pintype "output"))
      (node (ref "U1") (pin "9") (pinfunction "SA_2_9") (pintype "output"))
    )
    (net (code "45") (name "/R_YB") (class "Default")
      (node (ref "U$2") (pin "P$2") (pinfunction "B_P$2") (pintype "input"))
      (node (ref "U1") (pin "11") (pinfunction "SB_2_11") (pintype "output"))
      (node (ref "U1") (pin "24") (pinfunction "SB_24") (pintype "output"))
    )
    (net (code "46") (name "/R_YC") (class "Default")
      (node (ref "U$2") (pin "P$1") (pinfunction "A_P$1") (pintype "input"))
      (node (ref "U1") (pin "13") (pinfunction "SC_2_13") (pintype "output"))
      (node (ref "U1") (pin "22") (pinfunction "SC_22") (pintype "output"))
    )
    (net (code "47") (name "/SCL") (class "Default")
      (node (ref "R14") (pin "1") (pinfunction "1_1") (pintype "passive"))
      (node (ref "U$3") (pin "P$13") (pinfunction "SCL_P$13") (pintype "bidirectional"))
      (node (ref "U2") (pin "83") (pinfunction "PD2_83") (pintype "bidirectional"))
    )
    (net (code "48") (name "/SDA") (class "Default")
      (node (ref "R13") (pin "1") (pinfunction "1_1") (pintype "passive"))
      (node (ref "U$3") (pin "P$14") (pinfunction "SDA_P$14") (pintype "bidirectional"))
      (node (ref "U2") (pin "82") (pinfunction "PD1_82") (pintype "bidirectional"))
    )
    (net (code "49") (name "/SWCLK") (class "Default")
      (node (ref "J1") (pin "4") (pinfunction "4_4") (pintype "passive"))
      (node (ref "U2") (pin "76") (pinfunction "PA14_76") (pintype "bidirectional"))
    )
    (net (code "50") (name "/SWDIO") (class "Default")
      (node (ref "J1") (pin "6") (pinfunction "6_6") (pintype "passive"))
      (node (ref "U2") (pin "72") (pinfunction "PA13_72") (pintype "bidirectional"))
    )
    (net (code "51") (name "/UART_RX") (class "Default")
      (node (ref "J1") (pin "3") (pinfunction "3_3") (pintype "passive"))
      (node (ref "U2") (pin "69") (pinfunction "PA10_69") (pintype "bidirectional"))
    )
    (net (code "52") (name "/UART_TX") (class "Default")
      (node (ref "J1") (pin "5") (pinfunction "5_5") (pintype "passive"))
      (node (ref "U2") (pin "68") (pinfunction "PA9_68") (pintype "bidirectional"))
    )
    (net (code "53") (name "/USBDM") (class "Default")
      (node (ref "U2") (pin "70") (pinfunction "PA_11_70") (pintype "bidirectional"))
      (node (ref "USB") (pin "D-") (pinfunction "D-_D-") (pintype "bidirectional"))
    )
    (net (code "54") (name "/USBDP") (class "Default")
      (node (ref "R26") (pin "2") (pinfunction "2_2") (pintype "passive"))
      (node (ref "U2") (pin "71") (pinfunction "PA12_71") (pintype "bidirectional"))
      (node (ref "USB") (pin "D+") (pinfunction "D+_D+") (pintype "bidirectional"))
    )
    (net (code "55") (name "/VBAT") (class "Default")
      (node (ref "U2") (pin "6") (pinfunction "VBAT_6") (pintype "power_in"))
    )
    (net (code "56") (name "GND") (class "Default")
      (node (ref "C1") (pin "2") (pinfunction "2_2") (pintype "passive"))
      (node (ref "C10") (pin "-") (pinfunction "-_-") (pintype "passive"))
      (node (ref "C13") (pin "2") (pinfunction "2_2") (pintype "passive"))
      (node (ref "C15") (pin "2") (pinfunction "2_2") (pintype "passive"))
      (node (ref "C16") (pin "2") (pinfunction "2_2") (pintype "passive"))
      (node (ref "C17") (pin "1") (pinfunction "1_1") (pintype "passive"))
      (node (ref "C18") (pin "1") (pinfunction "1_1") (pintype "passive"))
      (node (ref "C19") (pin "2") (pinfunction "2_2") (pintype "passive"))
      (node (ref "C20") (pin "2") (pinfunction "2_2") (pintype "passive"))
      (node (ref "C21") (pin "2") (pinfunction "2_2") (pintype "passive"))
      (node (ref "C22") (pin "2") (pinfunction "2_2") (pintype "passive"))
      (node (ref "C23") (pin "1") (pinfunction "1_1") (pintype "passive"))
      (node (ref "C24") (pin "2") (pinfunction "2_2") (pintype "passive"))
      (node (ref "C25") (pin "1") (pinfunction "1_1") (pintype "passive"))
      (node (ref "C26") (pin "1") (pinfunction "1_1") (pintype "passive"))
      (node (ref "C27") (pin "2") (pinfunction "2_2") (pintype "passive"))
      (node (ref "C28") (pin "2") (pinfunction "2_2") (pintype "passive"))
      (node (ref "C29") (pin "2") (pinfunction "2_2") (pintype "passive"))
      (node (ref "C32") (pin "1") (pinfunction "1_1") (pintype "passive"))
      (node (ref "C33") (pin "1") (pinfunction "1_1") (pintype "passive"))
      (node (ref "C35") (pin "2") (pinfunction "2_2") (pintype "passive"))
      (node (ref "C4") (pin "-") (pinfunction "-_-") (pintype "passive"))
      (node (ref "C40") (pin "1") (pinfunction "1_1") (pintype "passive"))
      (node (ref "C41") (pin "1") (pinfunction "1_1") (pintype "passive"))
      (node (ref "C42") (pin "1") (pinfunction "1_1") (pintype "passive"))
      (node (ref "C43") (pin "1") (pinfunction "1_1") (pintype "passive"))
      (node (ref "C44") (pin "1") (pinfunction "1_1") (pintype "passive"))
      (node (ref "C5") (pin "2") (pinfunction "2_2") (pintype "passive"))
      (node (ref "C6") (pin "2") (pinfunction "2_2") (pintype "passive"))
      (node (ref "C7") (pin "-") (pinfunction "-_-") (pintype "passive"))
      (node (ref "C8") (pin "-") (pinfunction "-_-") (pintype "passive"))
      (node (ref "C9") (pin "2") (pinfunction "2_2") (pintype "passive"))
      (node (ref "J1") (pin "7") (pinfunction "7_7") (pintype "passive"))
      (node (ref "J1") (pin "8") (pinfunction "8_8") (pintype "passive"))
      (node (ref "JP3") (pin "1") (pinfunction "1_1") (pintype "passive"))
      (node (ref "LED10") (pin "C") (pinfunction "C_C") (pintype "passive"))
      (node (ref "LED11") (pin "C") (pinfunction "C_C") (pintype "passive"))
      (node (ref "LED12") (pin "C") (pinfunction "C_C") (pintype "passive"))
      (node (ref "LED9") (pin "C") (pinfunction "C_C") (pintype "passive"))
      (node (ref "L_ENCODER") (pin "1") (pinfunction "1_1") (pintype "passive"))
      (node (ref "L_ENCODER1") (pin "1") (pinfunction "1_1") (pintype "passive"))
      (node (ref "Q10") (pin "E") (pinfunction "E_E") (pintype "passive"))
      (node (ref "Q11") (pin "E") (pinfunction "E_E") (pintype "passive"))
      (node (ref "Q2") (pin "2") (pinfunction "S_2") (pintype "passive"))
      (node (ref "Q4") (pin "E") (pinfunction "E_E") (pintype "passive"))
      (node (ref "Q5") (pin "E") (pinfunction "E_E") (pintype "passive"))
      (node (ref "Q6") (pin "E") (pinfunction "E_E") (pintype "passive"))
      (node (ref "Q7") (pin "E") (pinfunction "E_E") (pintype "passive"))
      (node (ref "Q8") (pin "E") (pinfunction "E_E") (pintype "passive"))
      (node (ref "Q9") (pin "E") (pinfunction "E_E") (pintype "passive"))
      (node (ref "R1") (pin "1") (pinfunction "1_1") (pintype "passive"))
      (node (ref "R3") (pin "1") (pinfunction "1_1") (pintype "passive"))
      (node (ref "R36") (pin "1") (pinfunction "1_1") (pintype "passive"))
      (node (ref "R39") (pin "1") (pinfunction "1_1") (pintype "passive"))
      (node (ref "RESET") (pin "1") (pinfunction "1_1") (pintype "passive"))
      (node (ref "RESET") (pin "2") (pinfunction "2_2") (pintype "passive"))
      (node (ref "TP2") (pin "TP") (pinfunction "TP_TP") (pintype "input"))
      (node (ref "U$3") (pin "P$1") (pinfunction "SDO/SA0_P$1") (pintype "bidirectional"))
      (node (ref "U$3") (pin "P$2") (pinfunction "SDX_P$2") (pintype "bidirectional"))
      (node (ref "U$3") (pin "P$3") (pinfunction "SCX_P$3") (pintype "bidirectional"))
      (node (ref "U$3") (pin "P$6") (pinfunction "GND1_P$6") (pintype "bidirectional"))
      (node (ref "U$3") (pin "P$7") (pinfunction "GND2_P$7") (pintype "bidirectional"))
      (node (ref "U$4") (pin "P$2") (pinfunction "GND_P$2") (pintype "bidirectional"))
      (node (ref "U$4") (pin "P$5") (pinfunction "WP_P$5") (pintype "bidirectional"))
      (node (ref "U1") (pin "18") (pinfunction "GND_18") (pintype "passive"))
      (node (ref "U2") (pin "10") (pinfunction "VSS_2_10") (pintype "passive"))
      (node (ref "U2") (pin "19") (pinfunction "VSSA_19") (pintype "passive"))
      (node (ref "U2") (pin "26") (pinfunction "VSS_26") (pintype "passive"))
      (node (ref "U2") (pin "49") (pinfunction "VSS_4_49") (pintype "power_in"))
      (node (ref "U2") (pin "74") (pinfunction "VSS_2_74") (pintype "passive"))
      (node (ref "U2") (pin "99") (pinfunction "VSS_99") (pintype "passive"))
      (node (ref "U3") (pin "18") (pinfunction "GND_18") (pintype "passive"))
      (node (ref "U4") (pin "4") (pinfunction "GND_4") (pintype "bidirectional"))
      (node (ref "USB") (pin "GND") (pinfunction "GND_GND") (pintype "power_in"))
      (node (ref "USB") (pin "S1") (pinfunction "SHIELD_S1") (pintype "bidirectional"))
      (node (ref "USB") (pin "S2") (pinfunction "SHIELD_S2") (pintype "bidirectional"))
      (node (ref "USB") (pin "S3") (pinfunction "SHIELD_S3") (pintype "bidirectional"))
      (node (ref "USB") (pin "S4") (pinfunction "SHIELD_S4") (pintype "bidirectional"))
      (node (ref "USER") (pin "1") (pinfunction "1_1") (pintype "passive"))
      (node (ref "USER") (pin "2") (pinfunction "2_2") (pintype "passive"))
      (node (ref "X1") (pin "11") (pinfunction "1_11") (pintype "passive"))
      (node (ref "X1") (pin "12") (pinfunction "1_12") (pintype "passive"))
      (node (ref "X2") (pin "1") (pinfunction "1_1") (pintype "passive"))
      (node (ref "X2") (pin "2") (pinfunction "1_2") (pintype "passive"))
      (node (ref "X3") (pin "4") (pinfunction "S_4") (pintype "passive"))
      (node (ref "X4") (pin "4") (pinfunction "S_4") (pintype "passive"))
      (node (ref "X5") (pin "4") (pinfunction "S_4") (pintype "passive"))
    )
    (net (code "57") (name "Net-(D1-PadA)") (class "Default")
      (node (ref "D1") (pin "A") (pinfunction "A_A") (pintype "passive"))
      (node (ref "USB") (pin "VBUS") (pinfunction "VBUS_VBUS") (pintype "power_in"))
    )
    (net (code "58") (name "Net-(JP1-Pad1)") (class "Default")
      (node (ref "JP1") (pin "1") (pinfunction "1_1") (pintype "passive"))
      (node (ref "JP3") (pin "2") (pinfunction "2_2") (pintype "passive"))
    )
    (net (code "59") (name "Net-(L1-1)") (class "Default")
      (node (ref "C39") (pin "1") (pinfunction "1_1") (pintype "passive"))
      (node (ref "L1") (pin "P$1") (pinfunction "1_P$1") (pintype "passive"))
      (node (ref "U4") (pin "5") (pinfunction "SW_5") (pintype "bidirectional"))
    )
    (net (code "60") (name "Net-(LED1-PadA)") (class "Default")
      (node (ref "LED1") (pin "A") (pinfunction "A_A") (pintype "passive"))
      (node (ref "R5") (pin "1") (pinfunction "1_1") (pintype "passive"))
    )
    (net (code "61") (name "Net-(LED2-PadA)") (class "Default")
      (node (ref "LED2") (pin "A") (pinfunction "A_A") (pintype "passive"))
      (node (ref "R10") (pin "1") (pinfunction "1_1") (pintype "passive"))
    )
    (net (code "62") (name "Net-(LED3-PadA)") (class "Default")
      (node (ref "LED3") (pin "A") (pinfunction "A_A") (pintype "passive"))
      (node (ref "R12") (pin "1") (pinfunction "1_1") (pintype "passive"))
    )
    (net (code "63") (name "Net-(LED4-PadA)") (class "Default")
      (node (ref "LED4") (pin "A") (pinfunction "A_A") (pintype "passive"))
      (node (ref "R17") (pin "1") (pinfunction "1_1") (pintype "passive"))
    )
    (net (code "64") (name "Net-(LED5-PadA)") (class "Default")
      (node (ref "LED5") (pin "A") (pinfunction "A_A") (pintype "passive"))
      (node (ref "R19") (pin "1") (pinfunction "1_1") (pintype "passive"))
    )
    (net (code "65") (name "Net-(LED6-PadA)") (class "Default")
      (node (ref "LED6") (pin "A") (pinfunction "A_A") (pintype "passive"))
      (node (ref "R21") (pin "1") (pinfunction "1_1") (pintype "passive"))
    )
    (net (code "66") (name "Net-(LED7-PadA)") (class "Default")
      (node (ref "LED7") (pin "A") (pinfunction "A_A") (pintype "passive"))
      (node (ref "R23") (pin "1") (pinfunction "1_1") (pintype "passive"))
    )
    (net (code "67") (name "Net-(LED8-PadA)") (class "Default")
      (node (ref "LED8") (pin "A") (pinfunction "A_A") (pintype "passive"))
      (node (ref "R25") (pin "1") (pinfunction "1_1") (pintype "passive"))
    )
    (net (code "68") (name "Net-(LED9-PadA)") (class "Default")
      (node (ref "LED9") (pin "A") (pinfunction "A_A") (pintype "passive"))
      (node (ref "R9") (pin "1") (pinfunction "1_1") (pintype "passive"))
    )
    (net (code "69") (name "Net-(LED10-PadA)") (class "Default")
      (node (ref "LED10") (pin "A") (pinfunction "A_A") (pintype "passive"))
      (node (ref "R38") (pin "1") (pinfunction "1_1") (pintype "passive"))
    )
    (net (code "70") (name "Net-(LED11-PadA)") (class "Default")
      (node (ref "LED11") (pin "A") (pinfunction "A_A") (pintype "passive"))
      (node (ref "R28") (pin "1") (pinfunction "1_1") (pintype "passive"))
    )
    (net (code "71") (name "Net-(LED12-PadA)") (class "Default")
      (node (ref "LED12") (pin "A") (pinfunction "A_A") (pintype "passive"))
      (node (ref "R27") (pin "2") (pinfunction "2_2") (pintype "passive"))
    )
    (net (code "72") (name "Net-(U1-CP1)") (class "Default")
      (node (ref "C2") (pin "2") (pinfunction "2_2") (pintype "passive"))
      (node (ref "U1") (pin "20") (pinfunction "CP1_20") (pintype "passive"))
    )
    (net (code "73") (name "Net-(U1-CP2)") (class "Default")
      (node (ref "C2") (pin "1") (pinfunction "1_1") (pintype "passive"))
      (node (ref "U1") (pin "21") (pinfunction "CP2_21") (pintype "passive"))
    )
    (net (code "74") (name "Net-(U1-LSS)") (class "Default")
      (node (ref "R1") (pin "2") (pinfunction "2_2") (pintype "passive"))
      (node (ref "R8") (pin "1") (pinfunction "1_1") (pintype "passive"))
      (node (ref "U1") (pin "10") (pinfunction "LSS_2_10") (pintype "passive"))
      (node (ref "U1") (pin "12") (pinfunction "LSS_12") (pintype "passive"))
    )
    (net (code "75") (name "Net-(U1-VCP)") (class "Default")
      (node (ref "C3") (pin "1") (pinfunction "1_1") (pintype "passive"))
      (node (ref "U1") (pin "19") (pinfunction "VCP_19") (pintype "output"))
    )
    (net (code "76") (name "Net-(U1-VG)") (class "Default")
      (node (ref "C1") (pin "1") (pinfunction "1_1") (pintype "passive"))
      (node (ref "U1") (pin "14") (pinfunction "VG_14") (pintype "power_in"))
    )
    (net (code "77") (name "Net-(U2A-VCAP_1)") (class "Default")
      (node (ref "C23") (pin "2") (pinfunction "2_2") (pintype "passive"))
      (node (ref "U2") (pin "48") (pinfunction "VCAP_1_48") (pintype "power_in"))
    )
    (net (code "78") (name "Net-(U2B-VCAP_2)") (class "Default")
      (node (ref "C19") (pin "1") (pinfunction "1_1") (pintype "passive"))
      (node (ref "U2") (pin "73") (pinfunction "VCAP_2_73") (pintype "power_in"))
    )
    (net (code "79") (name "Net-(U3-CP1)") (class "Default")
      (node (ref "C30") (pin "2") (pinfunction "2_2") (pintype "passive"))
      (node (ref "U3") (pin "20") (pinfunction "CP1_20") (pintype "passive"))
    )
    (net (code "80") (name "Net-(U3-CP2)") (class "Default")
      (node (ref "C30") (pin "1") (pinfunction "1_1") (pintype "passive"))
      (node (ref "U3") (pin "21") (pinfunction "CP2_21") (pintype "passive"))
    )
    (net (code "81") (name "Net-(U3-LSS)") (class "Default")
      (node (ref "R36") (pin "2") (pinfunction "2_2") (pintype "passive"))
      (node (ref "R7") (pin "1") (pinfunction "1_1") (pintype "passive"))
      (node (ref "U3") (pin "10") (pinfunction "LSS_2_10") (pintype "passive"))
      (node (ref "U3") (pin "12") (pinfunction "LSS_12") (pintype "passive"))
    )
    (net (code "82") (name "Net-(U3-VCP)") (class "Default")
      (node (ref "C31") (pin "1") (pinfunction "1_1") (pintype "passive"))
      (node (ref "U3") (pin "19") (pinfunction "VCP_19") (pintype "output"))
    )
    (net (code "83") (name "Net-(U3-VG)") (class "Default")
      (node (ref "C13") (pin "1") (pinfunction "1_1") (pintype "passive"))
      (node (ref "U3") (pin "14") (pinfunction "VG_14") (pintype "power_in"))
    )
    (net (code "84") (name "Net-(U4-BST)") (class "Default")
      (node (ref "C39") (pin "2") (pinfunction "2_2") (pintype "passive"))
      (node (ref "U4") (pin "6") (pinfunction "BST_6") (pintype "bidirectional"))
    )
    (net (code "85") (name "VCC") (class "Default")
      (node (ref "C10") (pin "+") (pinfunction "+_+") (pintype "passive"))
      (node (ref "C17") (pin "2") (pinfunction "2_2") (pintype "passive"))
      (node (ref "C18") (pin "2") (pinfunction "2_2") (pintype "passive"))
      (node (ref "C3") (pin "2") (pinfunction "2_2") (pintype "passive"))
      (node (ref "C31") (pin "2") (pinfunction "2_2") (pintype "passive"))
      (node (ref "C32") (pin "2") (pinfunction "2_2") (pintype "passive"))
      (node (ref "C33") (pin "2") (pinfunction "2_2") (pintype "passive"))
      (node (ref "C4") (pin "+") (pinfunction "+_+") (pintype "passive"))
      (node (ref "C40") (pin "2") (pinfunction "2_2") (pintype "passive"))
      (node (ref "C41") (pin "2") (pinfunction "2_2") (pintype "passive"))
      (node (ref "D1") (pin "C") (pinfunction "C_C") (pintype "passive"))
      (node (ref "JP1") (pin "2") (pinfunction "2_2") (pintype "passive"))
      (node (ref "U1") (pin "23") (pinfunction "VIN_2_23") (pintype "power_in"))
      (node (ref "U1") (pin "25") (pinfunction "VIN_25") (pintype "power_in"))
      (node (ref "U3") (pin "23") (pinfunction "VIN_2_23") (pintype "power_in"))
      (node (ref "U3") (pin "25") (pinfunction "VIN_25") (pintype "power_in"))
      (node (ref "U4") (pin "2") (pinfunction "EN_2") (pintype "bidirectional"))
      (node (ref "U4") (pin "3") (pinfunction "VIN_3") (pintype "bidirectional"))
    )
    (net (code "86") (name "unconnected-(U$3-INT1-PadP$4)") (class "Default")
      (node (ref "U$3") (pin "P$4") (pinfunction "INT1_P$4") (pintype "bidirectional"))
    )
    (net (code "87") (name "unconnected-(U$3-INT2-PadP$9)") (class "Default")
      (node (ref "U$3") (pin "P$9") (pinfunction "INT2_P$9") (pintype "bidirectional"))
    )
    (net (code "88") (name "unconnected-(U$3-NC1-PadP$10)") (class "Default")
      (node (ref "U$3") (pin "P$10") (pinfunction "NC1_P$10") (pintype "bidirectional"))
    )
    (net (code "89") (name "unconnected-(U$3-NC2-PadP$11)") (class "Default")
      (node (ref "U$3") (pin "P$11") (pinfunction "NC2_P$11") (pintype "bidirectional"))
    )
    (net (code "90") (name "unconnected-(U$5-GND-PadP$3)") (class "Default")
      (node (ref "U$5") (pin "P$3") (pinfunction "GND_P$3") (pintype "bidirectional"))
    )
    (net (code "91") (name "unconnected-(U$5-PWM-PadP$1)") (class "Default")
      (node (ref "U$5") (pin "P$1") (pinfunction "PWM_P$1") (pintype "bidirectional"))
    )
    (net (code "92") (name "unconnected-(U$5-VCC-PadP$2)") (class "Default")
      (node (ref "U$5") (pin "P$2") (pinfunction "VCC_P$2") (pintype "bidirectional"))
    )
    (net (code "93") (name "unconnected-(U1-NFAULT-Pad1)") (class "Default")
      (node (ref "U1") (pin "1") (pinfunction "NFAULT_1") (pintype "output"))
    )
    (net (code "94") (name "unconnected-(U1-SOA-Pad15)") (class "Default")
      (node (ref "U1") (pin "15") (pinfunction "SOA_15") (pintype "output"))
    )
    (net (code "95") (name "unconnected-(U1-SOB-Pad16)") (class "Default")
      (node (ref "U1") (pin "16") (pinfunction "SOB_16") (pintype "output"))
    )
    (net (code "96") (name "unconnected-(U1-SOC-Pad17)") (class "Default")
      (node (ref "U1") (pin "17") (pinfunction "SOC_17") (pintype "output"))
    )
    (net (code "97") (name "unconnected-(U2A-PB2-Pad36)") (class "Default")
      (node (ref "U2") (pin "36") (pinfunction "PB2_36") (pintype "bidirectional"))
    )
    (net (code "98") (name "unconnected-(U2A-PB10-Pad46)") (class "Default")
      (node (ref "U2") (pin "46") (pinfunction "PB10_46") (pintype "bidirectional"))
    )
    (net (code "99") (name "unconnected-(U2A-PB11-Pad47)") (class "Default")
      (node (ref "U2") (pin "47") (pinfunction "PB11_47") (pintype "bidirectional"))
    )
    (net (code "100") (name "unconnected-(U2A-PC0-Pad15)") (class "Default")
      (node (ref "U2") (pin "15") (pinfunction "PC0_15") (pintype "bidirectional"))
    )
    (net (code "101") (name "unconnected-(U2A-PC1-Pad16)") (class "Default")
      (node (ref "U2") (pin "16") (pinfunction "PC1_16") (pintype "bidirectional"))
    )
    (net (code "102") (name "unconnected-(U2A-PC13-Pad7)") (class "Default")
      (node (ref "U2") (pin "7") (pinfunction "PC13_7") (pintype "bidirectional"))
    )
    (net (code "103") (name "unconnected-(U2A-PC14-Pad8)") (class "Default")
      (node (ref "U2") (pin "8") (pinfunction "PC14_8") (pintype "bidirectional"))
    )
    (net (code "104") (name "unconnected-(U2A-PE5-Pad4)") (class "Default")
      (node (ref "U2") (pin "4") (pinfunction "PE5_4") (pintype "bidirectional"))
    )
    (net (code "105") (name "unconnected-(U2A-PE6-Pad5)") (class "Default")
      (node (ref "U2") (pin "5") (pinfunction "PE6_5") (pintype "bidirectional"))
    )
    (net (code "106") (name "unconnected-(U2A-PE7-Pad37)") (class "Default")
      (node (ref "U2") (pin "37") (pinfunction "PE7_37") (pintype "bidirectional"))
    )
    (net (code "107") (name "unconnected-(U2A-PE8-Pad38)") (class "Default")
      (node (ref "U2") (pin "38") (pinfunction "PE8_38") (pintype "bidirectional"))
    )
    (net (code "108") (name "unconnected-(U2A-PE9-Pad39)") (class "Default")
      (node (ref "U2") (pin "39") (pinfunction "PE9_39") (pintype "bidirectional"))
    )
    (net (code "109") (name "unconnected-(U2A-PE10-Pad40)") (class "Default")
      (node (ref "U2") (pin "40") (pinfunction "PE10_40") (pintype "bidirectional"))
    )
    (net (code "110") (name "unconnected-(U2A-PE11-Pad41)") (class "Default")
      (node (ref "U2") (pin "41") (pinfunction "PE11_41") (pintype "bidirectional"))
    )
    (net (code "111") (name "unconnected-(U2A-PE12-Pad42)") (class "Default")
      (node (ref "U2") (pin "42") (pinfunction "PE12_42") (pintype "bidirectional"))
    )
    (net (code "112") (name "unconnected-(U2A-PE13-Pad43)") (class "Default")
      (node (ref "U2") (pin "43") (pinfunction "PE13_43") (pintype "bidirectional"))
    )
    (net (code "113") (name "unconnected-(U2A-PE14-Pad44)") (class "Default")
      (node (ref "U2") (pin "44") (pinfunction "PE14_44") (pintype "bidirectional"))
    )
    (net (code "114") (name "unconnected-(U2A-PE15-Pad45)") (class "Default")
      (node (ref "U2") (pin "45") (pinfunction "PE15_45") (pintype "bidirectional"))
    )
    (net (code "115") (name "unconnected-(U2B-PA15-Pad77)") (class "Default")
      (node (ref "U2") (pin "77") (pinfunction "PA15_77") (pintype "bidirectional"))
    )
    (net (code "116") (name "unconnected-(U2B-PB3-Pad89)") (class "Default")
      (node (ref "U2") (pin "89") (pinfunction "PB3_89") (pintype "bidirectional"))
    )
    (net (code "117") (name "unconnected-(U2B-PB4-Pad90)") (class "Default")
      (node (ref "U2") (pin "90") (pinfunction "PB4_90") (pintype "bidirectional"))
    )
    (net (code "118") (name "unconnected-(U2B-PB5-Pad91)") (class "Default")
      (node (ref "U2") (pin "91") (pinfunction "PB5_91") (pintype "bidirectional"))
    )
    (net (code "119") (name "unconnected-(U2B-PB12-Pad51)") (class "Default")
      (node (ref "U2") (pin "51") (pinfunction "PB12_51") (pintype "bidirectional"))
    )
    (net (code "120") (name "unconnected-(U2B-PB13-Pad52)") (class "Default")
      (node (ref "U2") (pin "52") (pinfunction "PB13_52") (pintype "bidirectional"))
    )
    (net (code "121") (name "unconnected-(U2B-PB14-Pad53)") (class "Default")
      (node (ref "U2") (pin "53") (pinfunction "PB14_53") (pintype "bidirectional"))
    )
    (net (code "122") (name "unconnected-(U2B-PC6-Pad63)") (class "Default")
      (node (ref "U2") (pin "63") (pinfunction "PC6_63") (pintype "bidirectional"))
    )
    (net (code "123") (name "unconnected-(U2B-PC10-Pad78)") (class "Default")
      (node (ref "U2") (pin "78") (pinfunction "PC10_78") (pintype "bidirectional"))
    )
    (net (code "124") (name "unconnected-(U2B-PC11-Pad79)") (class "Default")
      (node (ref "U2") (pin "79") (pinfunction "PC11_79") (pintype "bidirectional"))
    )
    (net (code "125") (name "unconnected-(U2B-PC12-Pad80)") (class "Default")
      (node (ref "U2") (pin "80") (pinfunction "PC12_80") (pintype "bidirectional"))
    )
    (net (code "126") (name "unconnected-(U2B-PD0-Pad81)") (class "Default")
      (node (ref "U2") (pin "81") (pinfunction "PD0_81") (pintype "bidirectional"))
    )
    (net (code "127") (name "unconnected-(U2B-PD5-Pad86)") (class "Default")
      (node (ref "U2") (pin "86") (pinfunction "PD5_86") (pintype "bidirectional"))
    )
    (net (code "128") (name "unconnected-(U2B-PD6-Pad87)") (class "Default")
      (node (ref "U2") (pin "87") (pinfunction "PD6_87") (pintype "bidirectional"))
    )
    (net (code "129") (name "unconnected-(U2B-PD7-Pad88)") (class "Default")
      (node (ref "U2") (pin "88") (pinfunction "PD7_88") (pintype "bidirectional"))
    )
    (net (code "130") (name "unconnected-(U2B-PD8-Pad55)") (class "Default")
      (node (ref "U2") (pin "55") (pinfunction "PD8_55") (pintype "bidirectional"))
    )
    (net (code "131") (name "unconnected-(U2B-PD9-Pad56)") (class "Default")
      (node (ref "U2") (pin "56") (pinfunction "PD9_56") (pintype "bidirectional"))
    )
    (net (code "132") (name "unconnected-(U2B-PD10-Pad57)") (class "Default")
      (node (ref "U2") (pin "57") (pinfunction "PD10_57") (pintype "bidirectional"))
    )
    (net (code "133") (name "unconnected-(U2B-PD11-Pad58)") (class "Default")
      (node (ref "U2") (pin "58") (pinfunction "PD11_58") (pintype "bidirectional"))
    )
    (net (code "134") (name "unconnected-(U2B-PD12-Pad59)") (class "Default")
      (node (ref "U2") (pin "59") (pinfunction "PD12_59") (pintype "bidirectional"))
    )
    (net (code "135") (name "unconnected-(U3-NFAULT-Pad1)") (class "Default")
      (node (ref "U3") (pin "1") (pinfunction "NFAULT_1") (pintype "output"))
    )
    (net (code "136") (name "unconnected-(U3-SOA-Pad15)") (class "Default")
      (node (ref "U3") (pin "15") (pinfunction "SOA_15") (pintype "output"))
    )
    (net (code "137") (name "unconnected-(U3-SOB-Pad16)") (class "Default")
      (node (ref "U3") (pin "16") (pinfunction "SOB_16") (pintype "output"))
    )
    (net (code "138") (name "unconnected-(U3-SOC-Pad17)") (class "Default")
      (node (ref "U3") (pin "17") (pinfunction "SOC_17") (pintype "output"))
    )
    (net (code "139") (name "unconnected-(USB-PadID)") (class "Default")
      (node (ref "USB") (pin "ID") (pinfunction "ID_ID") (pintype "bidirectional"))
    )
    (net (code "140") (name "unconnected-(USER-Pad3)") (class "Default")
      (node (ref "USER") (pin "3") (pinfunction "3_3") (pintype "passive"))
    )
  )
)
